# SkaarhojFaderboard.net
KiCad netlist of a schematic drawn in EAGLE
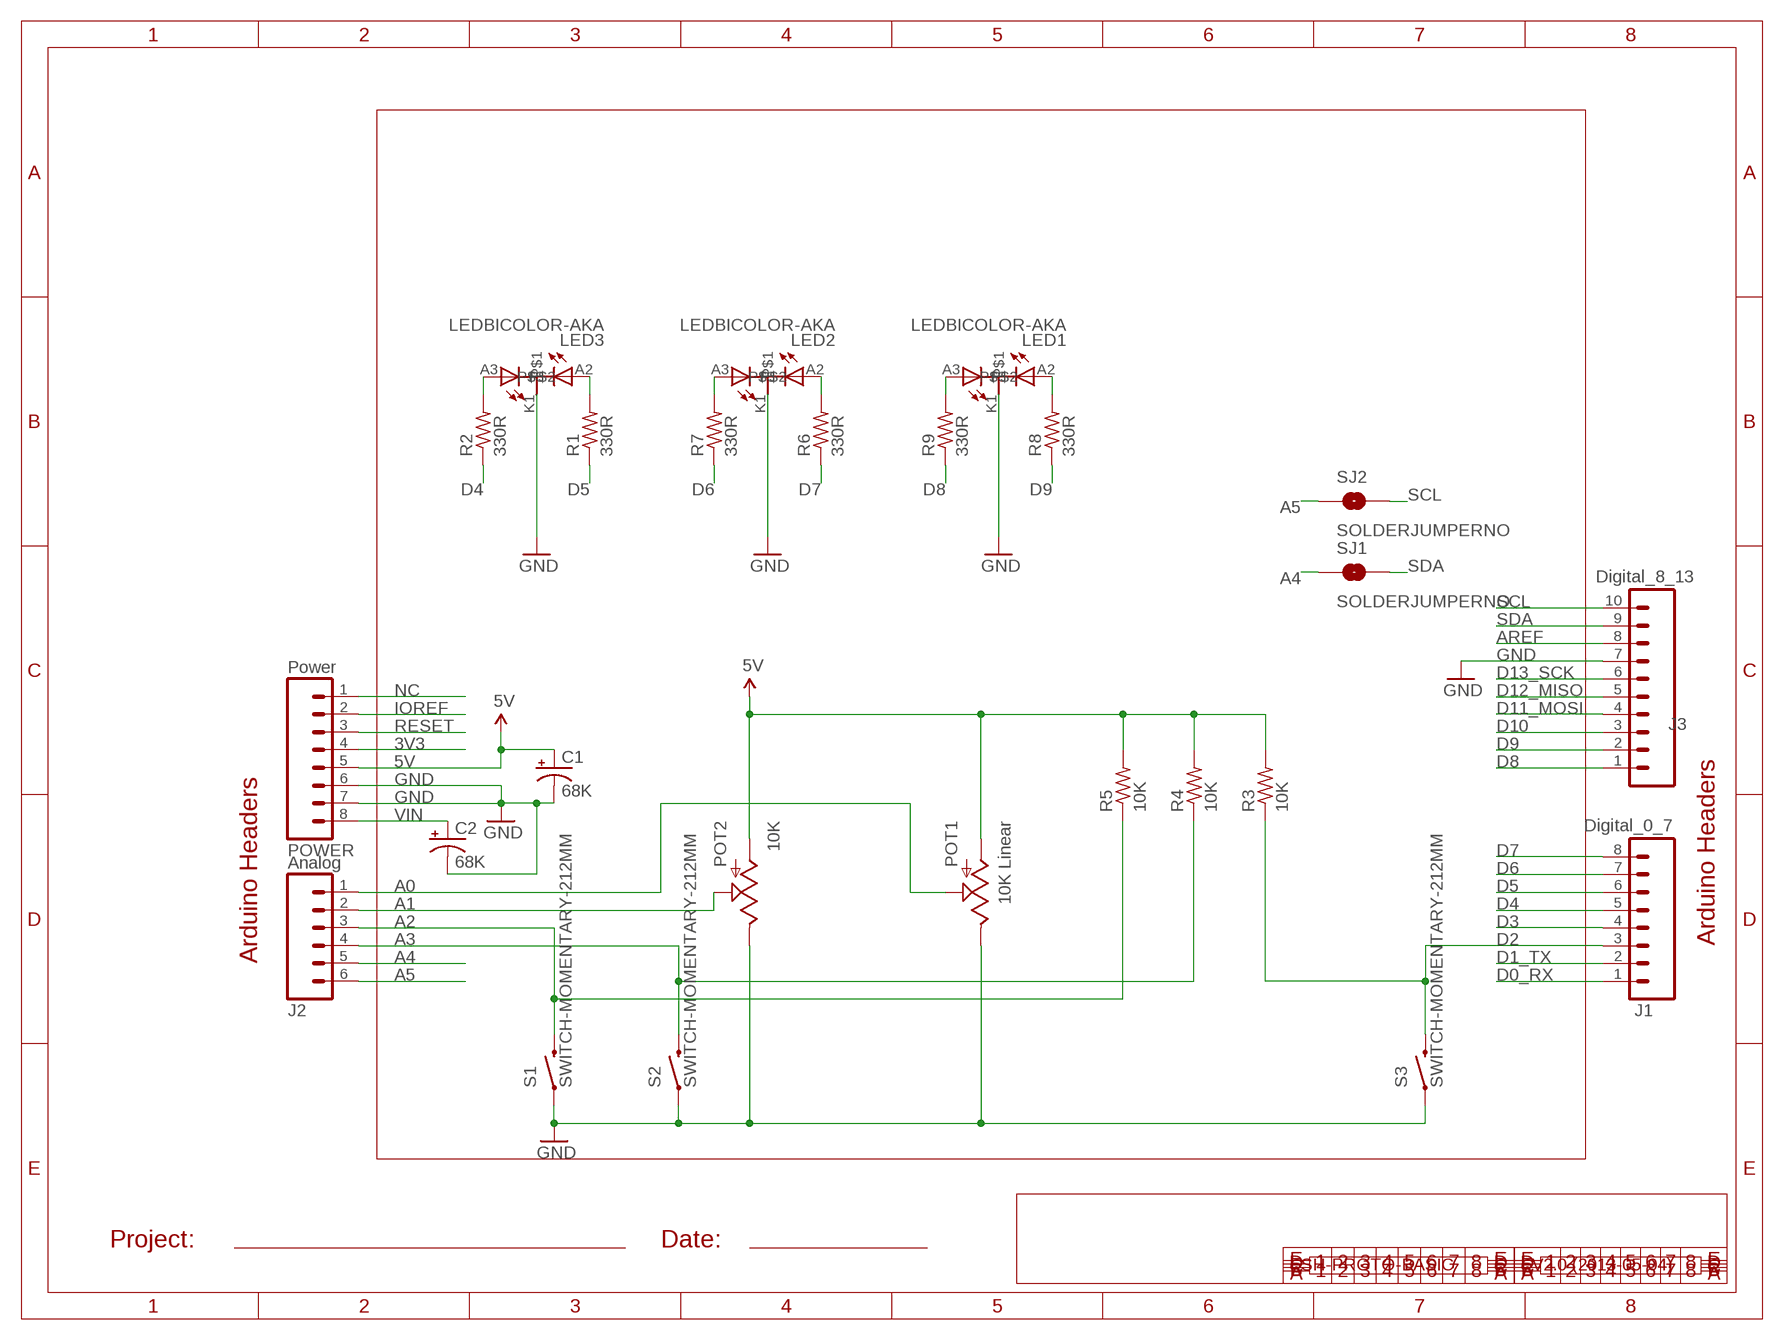
[diagram p0: schematic, sheet 1]

(export (version "E")
  (design (tool "Eeschema 10.0.6"))
  (components
    (comp (ref "C1")
      (value "68K")
      (footprint "eagle-import:CPOL-RADIAL-100UF-25V")
      (libsource (lib "eagle-import") (part "CAP_POLPTH1"))
    )
    (comp (ref "C2")
      (value "68K")
      (footprint "eagle-import:CPOL-RADIAL-100UF-25V")
      (libsource (lib "eagle-import") (part "CAP_POLPTH1"))
    )
    (comp (ref "J1")
      (value "Digital_0_7")
      (footprint "eagle-import:1X08")
      (libsource (lib "eagle-import") (part "M08"))
    )
    (comp (ref "J2")
      (value "Analog")
      (footprint "eagle-import:1X06")
      (libsource (lib "eagle-import") (part "M06SIP"))
    )
    (comp (ref "J3")
      (value "Digital_8_13")
      (footprint "eagle-import:1X10")
      (libsource (lib "eagle-import") (part "M100.1"))
    )
    (comp (ref "LED1")
      (value "LEDBICOLOR-AKA")
      (footprint "eagle-import:LED5MM-BICOLOR")
      (libsource (lib "eagle-import") (part "LEDBICOLOR-AKA"))
    )
    (comp (ref "LED2")
      (value "LEDBICOLOR-AKA")
      (footprint "eagle-import:LED5MM-BICOLOR")
      (libsource (lib "eagle-import") (part "LEDBICOLOR-AKA"))
    )
    (comp (ref "LED3")
      (value "LEDBICOLOR-AKA")
      (footprint "eagle-import:LED5MM-BICOLOR")
      (libsource (lib "eagle-import") (part "LEDBICOLOR-AKA"))
    )
    (comp (ref "POT1")
      (value "10K Linear")
      (footprint "eagle-import:SLIDER20")
      (libsource (lib "eagle-import") (part "SLIDER20"))
    )
    (comp (ref "POT2")
      (value "10K")
      (footprint "eagle-import:ALPS_POT")
      (libsource (lib "eagle-import") (part "POT"))
    )
    (comp (ref "POWER")
      (value "Power")
      (footprint "eagle-import:1X08")
      (libsource (lib "eagle-import") (part "freetronics-original_M08"))
    )
    (comp (ref "R1")
      (value "330R")
      (footprint "eagle-import:0207_10")
      (libsource (lib "eagle-import") (part "R-US_0207/10"))
    )
    (comp (ref "R2")
      (value "330R")
      (footprint "eagle-import:0207_10")
      (libsource (lib "eagle-import") (part "R-US_0207/10"))
    )
    (comp (ref "R3")
      (value "10K")
      (footprint "eagle-import:0207_10")
      (libsource (lib "eagle-import") (part "R-US_0207/10"))
    )
    (comp (ref "R4")
      (value "10K")
      (footprint "eagle-import:0207_10")
      (libsource (lib "eagle-import") (part "R-US_0207/10"))
    )
    (comp (ref "R5")
      (value "10K")
      (footprint "eagle-import:0207_10")
      (libsource (lib "eagle-import") (part "R-US_0207/10"))
    )
    (comp (ref "R6")
      (value "330R")
      (footprint "eagle-import:0207_10")
      (libsource (lib "eagle-import") (part "R-US_0207/10"))
    )
    (comp (ref "R7")
      (value "330R")
      (footprint "eagle-import:0207_10")
      (libsource (lib "eagle-import") (part "R-US_0207/10"))
    )
    (comp (ref "R8")
      (value "330R")
      (footprint "eagle-import:0207_10")
      (libsource (lib "eagle-import") (part "R-US_0207/10"))
    )
    (comp (ref "R9")
      (value "330R")
      (footprint "eagle-import:0207_10")
      (libsource (lib "eagle-import") (part "R-US_0207/10"))
    )
    (comp (ref "S1")
      (value "SWITCH-MOMENTARY-212MM")
      (footprint "eagle-import:TACTILE-PTH-12MM")
      (libsource (lib "eagle-import") (part "SWITCH-MOMENTARY-212MM"))
    )
    (comp (ref "S2")
      (value "SWITCH-MOMENTARY-212MM")
      (footprint "eagle-import:TACTILE-PTH-12MM")
      (libsource (lib "eagle-import") (part "SWITCH-MOMENTARY-212MM"))
    )
    (comp (ref "S3")
      (value "SWITCH-MOMENTARY-212MM")
      (footprint "eagle-import:TACTILE-PTH-12MM")
      (libsource (lib "eagle-import") (part "SWITCH-MOMENTARY-212MM"))
    )
    (comp (ref "SJ1")
      (value "SOLDERJUMPERNO")
      (footprint "eagle-import:SJ_2S-NO")
      (libsource (lib "eagle-import") (part "SOLDERJUMPERNO"))
    )
    (comp (ref "SJ2")
      (value "SOLDERJUMPERNO")
      (footprint "eagle-import:SJ_2S-NO")
      (libsource (lib "eagle-import") (part "SOLDERJUMPERNO"))
    )
  )
  (nets
    (net (code "1") (name "/3V3") (class "Default")
      (node (ref "POWER") (pin "4") (pinfunction "4_4") (pintype "passive"))
    )
    (net (code "2") (name "/A0") (class "Default")
      (node (ref "J2") (pin "1") (pinfunction "1_1") (pintype "passive"))
      (node (ref "POT1") (pin "2A") (pinfunction "S_2A") (pintype "passive"))
    )
    (net (code "3") (name "/A1") (class "Default")
      (node (ref "J2") (pin "2") (pinfunction "2_2") (pintype "passive"))
      (node (ref "POT2") (pin "P$2") (pinfunction "S_P$2") (pintype "passive"))
    )
    (net (code "4") (name "/A2") (class "Default")
      (node (ref "J2") (pin "3") (pinfunction "3_3") (pintype "passive"))
      (node (ref "R5") (pin "1") (pinfunction "1_1") (pintype "passive"))
      (node (ref "S1") (pin "3") (pinfunction "2_3") (pintype "passive"))
    )
    (net (code "5") (name "/A3") (class "Default")
      (node (ref "J2") (pin "4") (pinfunction "4_4") (pintype "passive"))
      (node (ref "R4") (pin "1") (pinfunction "1_1") (pintype "passive"))
      (node (ref "S2") (pin "3") (pinfunction "2_3") (pintype "passive"))
    )
    (net (code "6") (name "/A4") (class "Default")
      (node (ref "J2") (pin "5") (pinfunction "5_5") (pintype "passive"))
      (node (ref "SJ1") (pin "1") (pinfunction "1_1") (pintype "passive"))
    )
    (net (code "7") (name "/A5") (class "Default")
      (node (ref "J2") (pin "6") (pinfunction "6_6") (pintype "passive"))
      (node (ref "SJ2") (pin "1") (pinfunction "1_1") (pintype "passive"))
    )
    (net (code "8") (name "/AREF") (class "Default")
      (node (ref "J3") (pin "8") (pinfunction "8_8") (pintype "passive"))
    )
    (net (code "9") (name "/D0_RX") (class "Default")
      (node (ref "J1") (pin "1") (pinfunction "1_1") (pintype "passive"))
    )
    (net (code "10") (name "/D1_TX") (class "Default")
      (node (ref "J1") (pin "2") (pinfunction "2_2") (pintype "passive"))
    )
    (net (code "11") (name "/D2") (class "Default")
      (node (ref "J1") (pin "3") (pinfunction "3_3") (pintype "passive"))
      (node (ref "R3") (pin "1") (pinfunction "1_1") (pintype "passive"))
      (node (ref "S3") (pin "3") (pinfunction "2_3") (pintype "passive"))
    )
    (net (code "12") (name "/D3") (class "Default")
      (node (ref "J1") (pin "4") (pinfunction "4_4") (pintype "passive"))
    )
    (net (code "13") (name "/D4") (class "Default")
      (node (ref "J1") (pin "5") (pinfunction "5_5") (pintype "passive"))
      (node (ref "R2") (pin "1") (pinfunction "1_1") (pintype "passive"))
    )
    (net (code "14") (name "/D5") (class "Default")
      (node (ref "J1") (pin "6") (pinfunction "6_6") (pintype "passive"))
      (node (ref "R1") (pin "1") (pinfunction "1_1") (pintype "passive"))
    )
    (net (code "15") (name "/D6") (class "Default")
      (node (ref "J1") (pin "7") (pinfunction "7_7") (pintype "passive"))
      (node (ref "R7") (pin "1") (pinfunction "1_1") (pintype "passive"))
    )
    (net (code "16") (name "/D7") (class "Default")
      (node (ref "J1") (pin "8") (pinfunction "8_8") (pintype "passive"))
      (node (ref "R6") (pin "1") (pinfunction "1_1") (pintype "passive"))
    )
    (net (code "17") (name "/D8") (class "Default")
      (node (ref "J3") (pin "1") (pinfunction "1_1") (pintype "passive"))
      (node (ref "R9") (pin "1") (pinfunction "1_1") (pintype "passive"))
    )
    (net (code "18") (name "/D9") (class "Default")
      (node (ref "J3") (pin "2") (pinfunction "2_2") (pintype "passive"))
      (node (ref "R8") (pin "1") (pinfunction "1_1") (pintype "passive"))
    )
    (net (code "19") (name "/D10") (class "Default")
      (node (ref "J3") (pin "3") (pinfunction "3_3") (pintype "passive"))
    )
    (net (code "20") (name "/D11_MOSI") (class "Default")
      (node (ref "J3") (pin "4") (pinfunction "4_4") (pintype "passive"))
    )
    (net (code "21") (name "/D12_MISO") (class "Default")
      (node (ref "J3") (pin "5") (pinfunction "5_5") (pintype "passive"))
    )
    (net (code "22") (name "/D13_SCK") (class "Default")
      (node (ref "J3") (pin "6") (pinfunction "6_6") (pintype "passive"))
    )
    (net (code "23") (name "/IOREF") (class "Default")
      (node (ref "POWER") (pin "2") (pinfunction "2_2") (pintype "passive"))
    )
    (net (code "24") (name "/NC") (class "Default")
      (node (ref "POWER") (pin "1") (pinfunction "1_1") (pintype "passive"))
    )
    (net (code "25") (name "/RESET") (class "Default")
      (node (ref "POWER") (pin "3") (pinfunction "3_3") (pintype "passive"))
    )
    (net (code "26") (name "/SCL") (class "Default")
      (node (ref "J3") (pin "10") (pinfunction "10_10") (pintype "passive"))
      (node (ref "SJ2") (pin "2") (pinfunction "2_2") (pintype "passive"))
    )
    (net (code "27") (name "/SDA") (class "Default")
      (node (ref "J3") (pin "9") (pinfunction "9_9") (pintype "passive"))
      (node (ref "SJ1") (pin "2") (pinfunction "2_2") (pintype "passive"))
    )
    (net (code "28") (name "/VIN") (class "Default")
      (node (ref "C2") (pin "1") (pinfunction "+_1") (pintype "passive"))
      (node (ref "POWER") (pin "8") (pinfunction "8_8") (pintype "passive"))
    )
    (net (code "29") (name "5V") (class "Default")
      (node (ref "C1") (pin "1") (pinfunction "+_1") (pintype "passive"))
      (node (ref "POT1") (pin "3") (pinfunction "A_3") (pintype "passive"))
      (node (ref "POT2") (pin "P$3") (pinfunction "A_P$3") (pintype "passive"))
      (node (ref "POWER") (pin "5") (pinfunction "5_5") (pintype "passive"))
      (node (ref "R3") (pin "2") (pinfunction "2_2") (pintype "passive"))
      (node (ref "R4") (pin "2") (pinfunction "2_2") (pintype "passive"))
      (node (ref "R5") (pin "2") (pinfunction "2_2") (pintype "passive"))
    )
    (net (code "30") (name "GND") (class "Default")
      (node (ref "C1") (pin "2") (pinfunction "-_2") (pintype "passive"))
      (node (ref "C2") (pin "2") (pinfunction "-_2") (pintype "passive"))
      (node (ref "J3") (pin "7") (pinfunction "7_7") (pintype "passive"))
      (node (ref "LED1") (pin "K1") (pinfunction "P$1_K1") (pintype "bidirectional"))
      (node (ref "LED2") (pin "K1") (pinfunction "P$1_K1") (pintype "bidirectional"))
      (node (ref "LED3") (pin "K1") (pinfunction "P$1_K1") (pintype "bidirectional"))
      (node (ref "POT1") (pin "1") (pinfunction "E_1") (pintype "passive"))
      (node (ref "POT2") (pin "P$1") (pinfunction "E_P$1") (pintype "passive"))
      (node (ref "POWER") (pin "6") (pinfunction "6_6") (pintype "passive"))
      (node (ref "POWER") (pin "7") (pinfunction "7_7") (pintype "passive"))
      (node (ref "S1") (pin "1") (pinfunction "1_1") (pintype "passive"))
      (node (ref "S2") (pin "1") (pinfunction "1_1") (pintype "passive"))
      (node (ref "S3") (pin "1") (pinfunction "1_1") (pintype "passive"))
    )
    (net (code "31") (name "Net-(LED1-P$2)") (class "Default")
      (node (ref "LED1") (pin "A2") (pinfunction "P$2_A2") (pintype "bidirectional"))
      (node (ref "R8") (pin "2") (pinfunction "2_2") (pintype "passive"))
    )
    (net (code "32") (name "Net-(LED1-P$3)") (class "Default")
      (node (ref "LED1") (pin "A3") (pinfunction "P$3_A3") (pintype "bidirectional"))
      (node (ref "R9") (pin "2") (pinfunction "2_2") (pintype "passive"))
    )
    (net (code "33") (name "Net-(LED2-P$2)") (class "Default")
      (node (ref "LED2") (pin "A2") (pinfunction "P$2_A2") (pintype "bidirectional"))
      (node (ref "R6") (pin "2") (pinfunction "2_2") (pintype "passive"))
    )
    (net (code "34") (name "Net-(LED2-P$3)") (class "Default")
      (node (ref "LED2") (pin "A3") (pinfunction "P$3_A3") (pintype "bidirectional"))
      (node (ref "R7") (pin "2") (pinfunction "2_2") (pintype "passive"))
    )
    (net (code "35") (name "Net-(LED3-P$2)") (class "Default")
      (node (ref "LED3") (pin "A2") (pinfunction "P$2_A2") (pintype "bidirectional"))
      (node (ref "R1") (pin "2") (pinfunction "2_2") (pintype "passive"))
    )
    (net (code "36") (name "Net-(LED3-P$3)") (class "Default")
      (node (ref "LED3") (pin "A3") (pinfunction "P$3_A3") (pintype "bidirectional"))
      (node (ref "R2") (pin "2") (pinfunction "2_2") (pintype "passive"))
    )
  )
)
